# IEC-Breakout.net
KiCad netlist of a schematic drawn in EAGLE
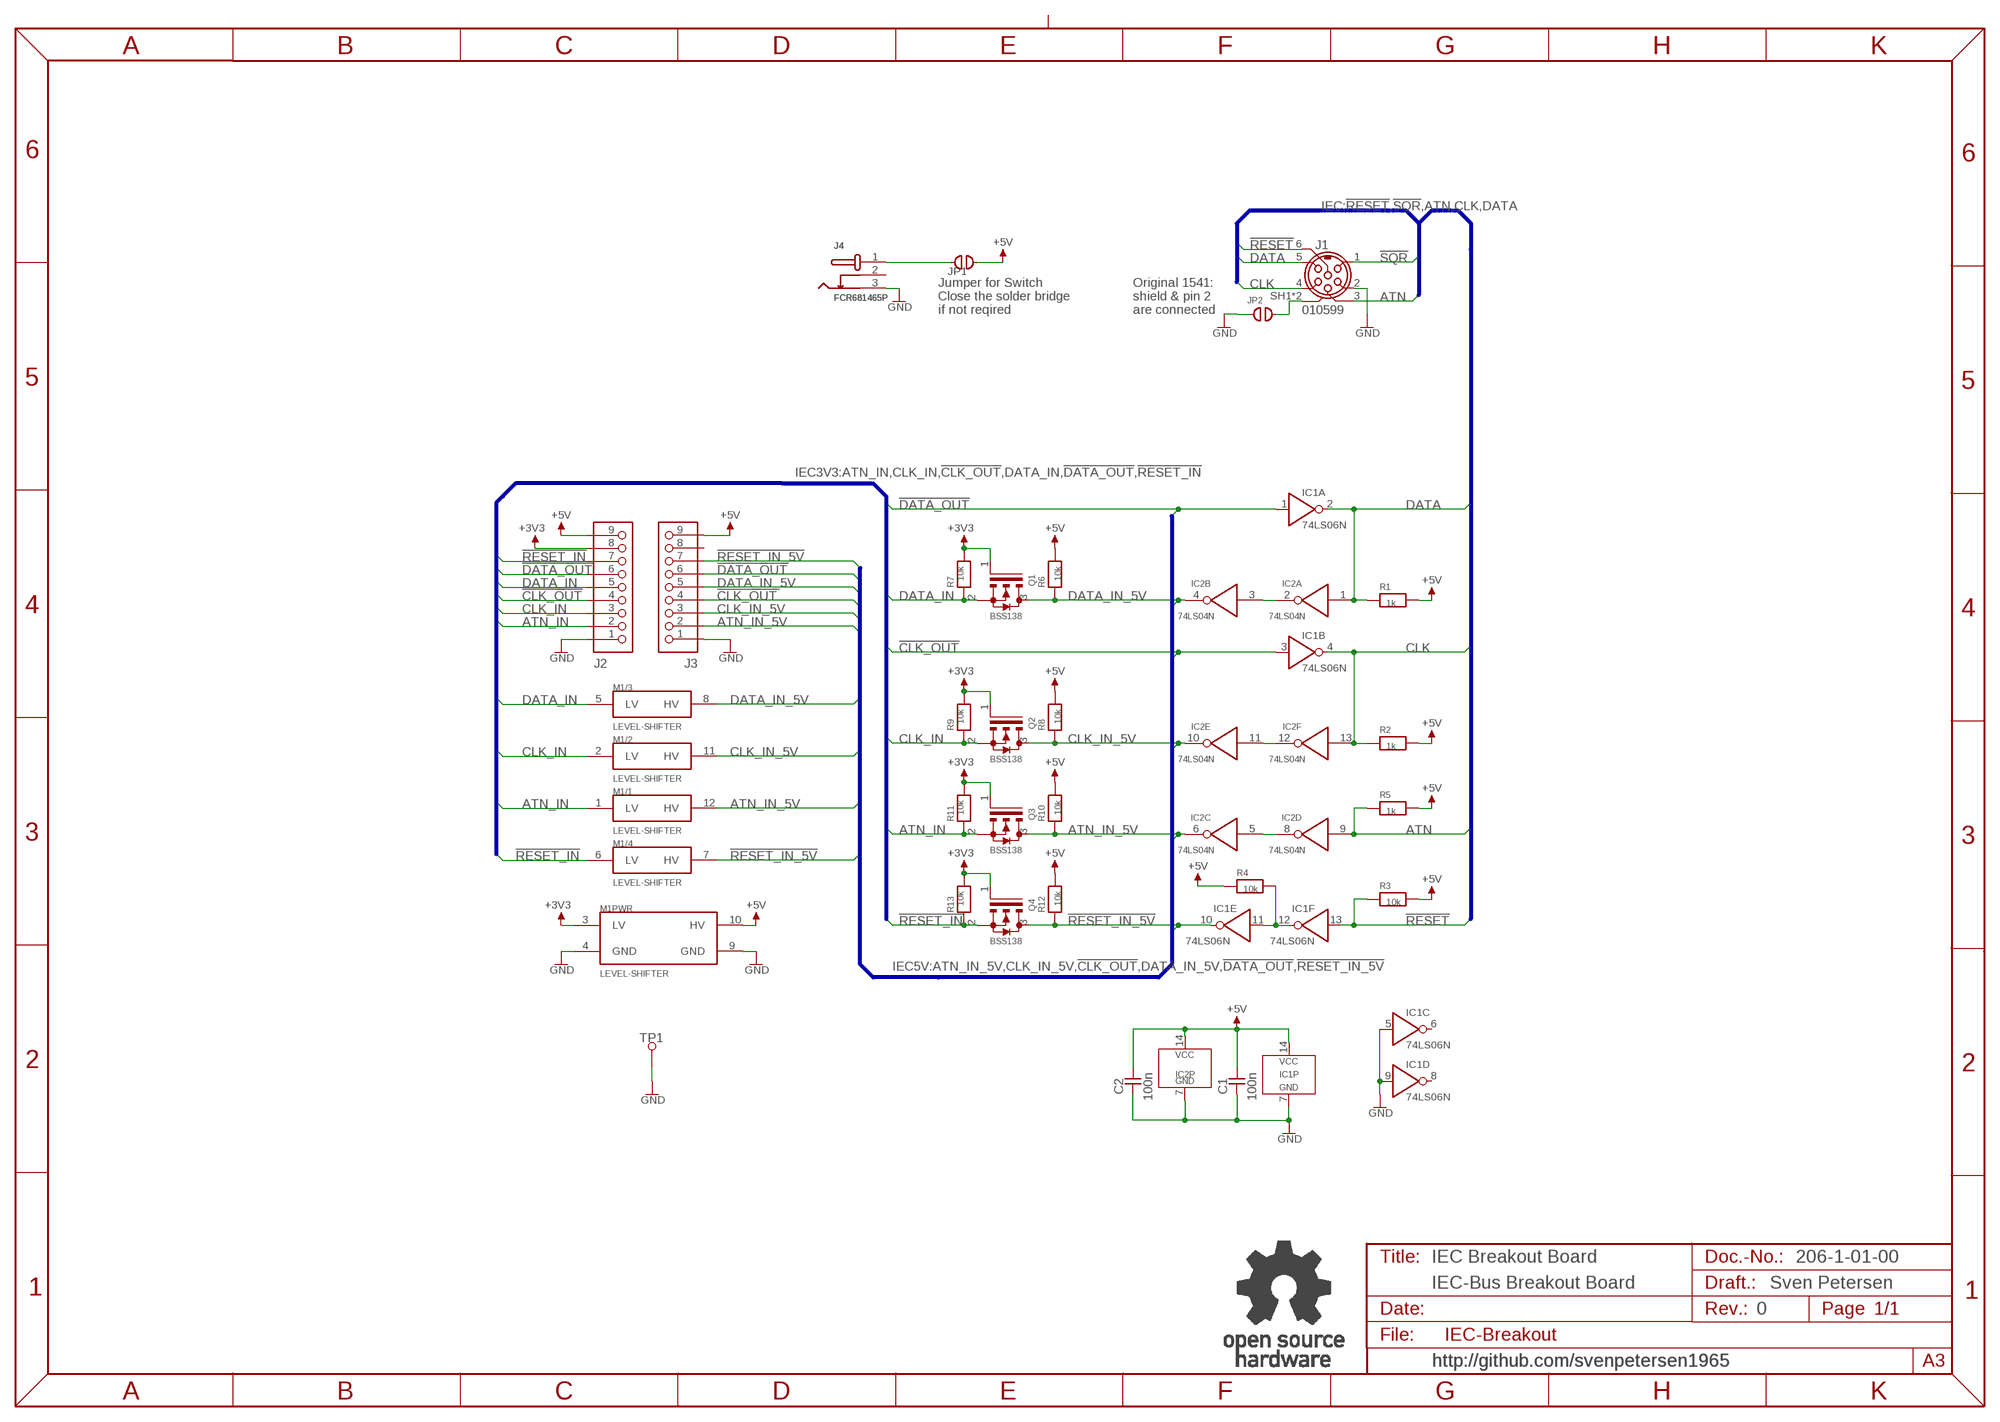
[diagram p0: schematic, sheet 1]

(export (version "E")
  (design (tool "Eeschema 10.0.6"))
  (components
    (comp (ref "C1")
      (value "100n")
      (footprint "eagle-import:C-2,5")
      (libsource (lib "eagle-import") (part "CAP01"))
    )
    (comp (ref "C2")
      (value "100n")
      (footprint "eagle-import:C-2,5")
      (libsource (lib "eagle-import") (part "CAP01"))
    )
    (comp (ref "IC1")
      (value "74LS06N")
      (footprint "eagle-import:DIL-14")
      (libsource (lib "eagle-import") (part "7406N"))
    )
    (comp (ref "IC2")
      (value "74LS04N")
      (footprint "eagle-import:DIL-14")
      (libsource (lib "eagle-import") (part "7404N"))
    )
    (comp (ref "J1")
      (value "010599")
      (footprint "eagle-import:010599")
      (libsource (lib "eagle-import") (part "010599"))
    )
    (comp (ref "J2")
      (value "PINHD-1X9")
      (footprint "eagle-import:1X09")
      (libsource (lib "eagle-import") (part "PINHD-1X9"))
    )
    (comp (ref "J3")
      (value "PINHD-1X9")
      (footprint "eagle-import:1X09")
      (libsource (lib "eagle-import") (part "PINHD-1X9"))
    )
    (comp (ref "J4")
      (value "FCR681465P")
      (footprint "eagle-import:FCR681465P")
      (libsource (lib "eagle-import") (part "FCR681465P"))
    )
    (comp (ref "JP1")
      (value "COMBI_2P")
      (footprint "eagle-import:COMBI-2P")
      (libsource (lib "eagle-import") (part "COMBI_2P"))
    )
    (comp (ref "JP2")
      (value "OPEN")
      (footprint "eagle-import:CP_OP")
      (libsource (lib "eagle-import") (part "OPEN"))
    )
    (comp (ref "M1")
      (value "LEVEL-SHIFTER")
      (footprint "eagle-import:L-SHIFTER")
      (libsource (lib "eagle-import") (part "LEVEL-SHIFTER"))
    )
    (comp (ref "Q1")
      (value "BSS138")
      (footprint "eagle-import:SOT23")
      (libsource (lib "eagle-import") (part "BSS138"))
    )
    (comp (ref "Q2")
      (value "BSS138")
      (footprint "eagle-import:SOT23")
      (libsource (lib "eagle-import") (part "BSS138"))
    )
    (comp (ref "Q3")
      (value "BSS138")
      (footprint "eagle-import:SOT23")
      (libsource (lib "eagle-import") (part "BSS138"))
    )
    (comp (ref "Q4")
      (value "BSS138")
      (footprint "eagle-import:SOT23")
      (libsource (lib "eagle-import") (part "BSS138"))
    )
    (comp (ref "R1")
      (value "1k")
      (footprint "eagle-import:R-10")
      (libsource (lib "eagle-import") (part "RES04"))
    )
    (comp (ref "R2")
      (value "1k")
      (footprint "eagle-import:R-10")
      (libsource (lib "eagle-import") (part "RES04"))
    )
    (comp (ref "R3")
      (value "10k")
      (footprint "eagle-import:R-10")
      (libsource (lib "eagle-import") (part "RES04"))
    )
    (comp (ref "R4")
      (value "10k")
      (footprint "eagle-import:R-10")
      (libsource (lib "eagle-import") (part "RES04"))
    )
    (comp (ref "R5")
      (value "1k")
      (footprint "eagle-import:R-10")
      (libsource (lib "eagle-import") (part "RES04"))
    )
    (comp (ref "R6")
      (value "10k")
      (footprint "eagle-import:0805")
      (libsource (lib "eagle-import") (part "R-0805"))
    )
    (comp (ref "R7")
      (value "10k")
      (footprint "eagle-import:0805")
      (libsource (lib "eagle-import") (part "R-0805"))
    )
    (comp (ref "R8")
      (value "10k")
      (footprint "eagle-import:0805")
      (libsource (lib "eagle-import") (part "R-0805"))
    )
    (comp (ref "R9")
      (value "10k")
      (footprint "eagle-import:0805")
      (libsource (lib "eagle-import") (part "R-0805"))
    )
    (comp (ref "R10")
      (value "10k")
      (footprint "eagle-import:0805")
      (libsource (lib "eagle-import") (part "R-0805"))
    )
    (comp (ref "R11")
      (value "10k")
      (footprint "eagle-import:0805")
      (libsource (lib "eagle-import") (part "R-0805"))
    )
    (comp (ref "R12")
      (value "10k")
      (footprint "eagle-import:0805")
      (libsource (lib "eagle-import") (part "R-0805"))
    )
    (comp (ref "R13")
      (value "10k")
      (footprint "eagle-import:0805")
      (libsource (lib "eagle-import") (part "R-0805"))
    )
    (comp (ref "TP1")
      (value "L1,2_R")
      (footprint "eagle-import:1,2MM_R")
      (libsource (lib "eagle-import") (part "L1,2_R"))
    )
    (comp (ref "U$31")
      (value "OPEN_SOURCE_HW")
      (footprint "eagle-import:OPENHW")
      (libsource (lib "eagle-import") (part "OPEN_SOURCE_HW"))
    )
  )
  (nets
    (net (code "4") (name "+3V3") (class "Default")
      (node (ref "J2") (pin "8") (pinfunction "8_8") (pintype "passive"))
      (node (ref "M1") (pin "3") (pinfunction "LV_3") (pintype "bidirectional"))
      (node (ref "Q1") (pin "1") (pinfunction "G_1") (pintype "bidirectional"))
      (node (ref "Q2") (pin "1") (pinfunction "G_1") (pintype "bidirectional"))
      (node (ref "Q3") (pin "1") (pinfunction "G_1") (pintype "bidirectional"))
      (node (ref "Q4") (pin "1") (pinfunction "G_1") (pintype "bidirectional"))
      (node (ref "R11") (pin "2") (pinfunction "2_2") (pintype "passive"))
      (node (ref "R13") (pin "2") (pinfunction "2_2") (pintype "passive"))
      (node (ref "R7") (pin "2") (pinfunction "2_2") (pintype "passive"))
      (node (ref "R9") (pin "2") (pinfunction "2_2") (pintype "passive"))
    )
    (net (code "5") (name "+5V") (class "Default")
      (node (ref "C1") (pin "2") (pinfunction "2_2") (pintype "passive"))
      (node (ref "C2") (pin "2") (pinfunction "2_2") (pintype "passive"))
      (node (ref "IC1") (pin "14") (pinfunction "VCC_14") (pintype "bidirectional"))
      (node (ref "IC2") (pin "14") (pinfunction "VCC_14") (pintype "bidirectional"))
      (node (ref "J2") (pin "9") (pinfunction "9_9") (pintype "passive"))
      (node (ref "J3") (pin "9") (pinfunction "9_9") (pintype "passive"))
      (node (ref "JP1") (pin "2") (pinfunction "2_2") (pintype "passive"))
      (node (ref "M1") (pin "10") (pinfunction "HV_10") (pintype "bidirectional"))
      (node (ref "R1") (pin "2") (pinfunction "2_2") (pintype "passive"))
      (node (ref "R10") (pin "2") (pinfunction "2_2") (pintype "passive"))
      (node (ref "R12") (pin "2") (pinfunction "2_2") (pintype "passive"))
      (node (ref "R2") (pin "2") (pinfunction "2_2") (pintype "passive"))
      (node (ref "R3") (pin "2") (pinfunction "2_2") (pintype "passive"))
      (node (ref "R4") (pin "1") (pinfunction "1_1") (pintype "passive"))
      (node (ref "R5") (pin "2") (pinfunction "2_2") (pintype "passive"))
      (node (ref "R6") (pin "2") (pinfunction "2_2") (pintype "passive"))
      (node (ref "R8") (pin "2") (pinfunction "2_2") (pintype "passive"))
    )
    (net (code "6") (name "/ATN") (class "Default")
      (node (ref "IC2") (pin "9") (pinfunction "I_9") (pintype "input"))
      (node (ref "J1") (pin "3") (pinfunction "3_3") (pintype "bidirectional"))
      (node (ref "R5") (pin "1") (pinfunction "1_1") (pintype "passive"))
    )
    (net (code "7") (name "/ATN_IN") (class "Default")
      (node (ref "J2") (pin "2") (pinfunction "2_2") (pintype "passive"))
      (node (ref "M1") (pin "1") (pinfunction "LV_1") (pintype "bidirectional"))
      (node (ref "Q3") (pin "2") (pinfunction "S_2") (pintype "bidirectional"))
      (node (ref "R11") (pin "1") (pinfunction "1_1") (pintype "passive"))
    )
    (net (code "8") (name "/ATN_IN_5V") (class "Default")
      (node (ref "IC2") (pin "6") (pinfunction "O_6") (pintype "output"))
      (node (ref "J3") (pin "2") (pinfunction "2_2") (pintype "passive"))
      (node (ref "M1") (pin "12") (pinfunction "HV_12") (pintype "bidirectional"))
      (node (ref "Q3") (pin "3") (pinfunction "D_3") (pintype "bidirectional"))
      (node (ref "R10") (pin "1") (pinfunction "1_1") (pintype "passive"))
    )
    (net (code "9") (name "/CLK") (class "Default")
      (node (ref "IC1") (pin "4") (pinfunction "O_4") (pintype "open_collector"))
      (node (ref "IC2") (pin "13") (pinfunction "I_13") (pintype "input"))
      (node (ref "J1") (pin "4") (pinfunction "4_4") (pintype "bidirectional"))
      (node (ref "R2") (pin "1") (pinfunction "1_1") (pintype "passive"))
    )
    (net (code "10") (name "/CLK_IN") (class "Default")
      (node (ref "J2") (pin "3") (pinfunction "3_3") (pintype "passive"))
      (node (ref "M1") (pin "2") (pinfunction "LV_2") (pintype "bidirectional"))
      (node (ref "Q2") (pin "2") (pinfunction "S_2") (pintype "bidirectional"))
      (node (ref "R9") (pin "1") (pinfunction "1_1") (pintype "passive"))
    )
    (net (code "11") (name "/CLK_IN_5V") (class "Default")
      (node (ref "IC2") (pin "10") (pinfunction "O_10") (pintype "output"))
      (node (ref "J3") (pin "3") (pinfunction "3_3") (pintype "passive"))
      (node (ref "M1") (pin "11") (pinfunction "HV_11") (pintype "bidirectional"))
      (node (ref "Q2") (pin "3") (pinfunction "D_3") (pintype "bidirectional"))
      (node (ref "R8") (pin "1") (pinfunction "1_1") (pintype "passive"))
    )
    (net (code "12") (name "/DATA") (class "Default")
      (node (ref "IC1") (pin "2") (pinfunction "O_2") (pintype "open_collector"))
      (node (ref "IC2") (pin "1") (pinfunction "I_1") (pintype "input"))
      (node (ref "J1") (pin "5") (pinfunction "5_5") (pintype "bidirectional"))
      (node (ref "R1") (pin "1") (pinfunction "1_1") (pintype "passive"))
    )
    (net (code "13") (name "/DATA_IN") (class "Default")
      (node (ref "J2") (pin "5") (pinfunction "5_5") (pintype "passive"))
      (node (ref "M1") (pin "5") (pinfunction "LV_5") (pintype "bidirectional"))
      (node (ref "Q1") (pin "2") (pinfunction "S_2") (pintype "bidirectional"))
      (node (ref "R7") (pin "1") (pinfunction "1_1") (pintype "passive"))
    )
    (net (code "14") (name "/DATA_IN_5V") (class "Default")
      (node (ref "IC2") (pin "4") (pinfunction "O_4") (pintype "output"))
      (node (ref "J3") (pin "5") (pinfunction "5_5") (pintype "passive"))
      (node (ref "M1") (pin "8") (pinfunction "HV_8") (pintype "bidirectional"))
      (node (ref "Q1") (pin "3") (pinfunction "D_3") (pintype "bidirectional"))
      (node (ref "R6") (pin "1") (pinfunction "1_1") (pintype "passive"))
    )
    (net (code "18") (name "/~{CLK_OUT}") (class "Default")
      (node (ref "IC1") (pin "3") (pinfunction "I_3") (pintype "input"))
      (node (ref "J2") (pin "4") (pinfunction "4_4") (pintype "passive"))
      (node (ref "J3") (pin "4") (pinfunction "4_4") (pintype "passive"))
    )
    (net (code "19") (name "/~{DATA_OUT}") (class "Default")
      (node (ref "IC1") (pin "1") (pinfunction "I_1") (pintype "input"))
      (node (ref "J2") (pin "6") (pinfunction "6_6") (pintype "passive"))
      (node (ref "J3") (pin "6") (pinfunction "6_6") (pintype "passive"))
    )
    (net (code "20") (name "/~{RESET_IN_5V}") (class "Default")
      (node (ref "IC1") (pin "10") (pinfunction "O_10") (pintype "open_collector"))
      (node (ref "J3") (pin "7") (pinfunction "7_7") (pintype "passive"))
      (node (ref "M1") (pin "7") (pinfunction "HV_7") (pintype "bidirectional"))
      (node (ref "Q4") (pin "3") (pinfunction "D_3") (pintype "bidirectional"))
      (node (ref "R12") (pin "1") (pinfunction "1_1") (pintype "passive"))
    )
    (net (code "21") (name "/~{RESET_IN}") (class "Default")
      (node (ref "J2") (pin "7") (pinfunction "7_7") (pintype "passive"))
      (node (ref "M1") (pin "6") (pinfunction "LV_6") (pintype "bidirectional"))
      (node (ref "Q4") (pin "2") (pinfunction "S_2") (pintype "bidirectional"))
      (node (ref "R13") (pin "1") (pinfunction "1_1") (pintype "passive"))
    )
    (net (code "22") (name "/~{RESET}") (class "Default")
      (node (ref "IC1") (pin "13") (pinfunction "I_13") (pintype "input"))
      (node (ref "J1") (pin "6") (pinfunction "6_6") (pintype "bidirectional"))
      (node (ref "R3") (pin "1") (pinfunction "1_1") (pintype "passive"))
    )
    (net (code "23") (name "/~{SQR}") (class "Default")
      (node (ref "J1") (pin "1") (pinfunction "1_1") (pintype "bidirectional"))
    )
    (net (code "24") (name "GND") (class "Default")
      (node (ref "C1") (pin "1") (pinfunction "1_1") (pintype "passive"))
      (node (ref "C2") (pin "1") (pinfunction "1_1") (pintype "passive"))
      (node (ref "IC1") (pin "5") (pinfunction "I_5") (pintype "input"))
      (node (ref "IC1") (pin "7") (pinfunction "GND_7") (pintype "bidirectional"))
      (node (ref "IC1") (pin "9") (pinfunction "I_9") (pintype "input"))
      (node (ref "IC2") (pin "7") (pinfunction "GND_7") (pintype "bidirectional"))
      (node (ref "J1") (pin "2") (pinfunction "2_2") (pintype "bidirectional"))
      (node (ref "J2") (pin "1") (pinfunction "1_1") (pintype "passive"))
      (node (ref "J3") (pin "1") (pinfunction "1_1") (pintype "passive"))
      (node (ref "J4") (pin "3") (pinfunction "3_3") (pintype "bidirectional"))
      (node (ref "JP2") (pin "1") (pinfunction "1_1") (pintype "passive"))
      (node (ref "M1") (pin "4") (pinfunction "GND_4") (pintype "bidirectional"))
      (node (ref "M1") (pin "9") (pinfunction "GND_9") (pintype "bidirectional"))
      (node (ref "TP1") (pin "1") (pinfunction "1_1") (pintype "passive"))
    )
    (net (code "25") (name "Net-(IC1E-I)") (class "Default")
      (node (ref "IC1") (pin "11") (pinfunction "I_11") (pintype "input"))
      (node (ref "IC1") (pin "12") (pinfunction "O_12") (pintype "open_collector"))
      (node (ref "R4") (pin "2") (pinfunction "2_2") (pintype "passive"))
    )
    (net (code "26") (name "Net-(IC2A-O)") (class "Default")
      (node (ref "IC2") (pin "2") (pinfunction "O_2") (pintype "output"))
      (node (ref "IC2") (pin "3") (pinfunction "I_3") (pintype "input"))
    )
    (net (code "27") (name "Net-(IC2C-I)") (class "Default")
      (node (ref "IC2") (pin "5") (pinfunction "I_5") (pintype "input"))
      (node (ref "IC2") (pin "8") (pinfunction "O_8") (pintype "output"))
    )
    (net (code "28") (name "Net-(IC2E-I)") (class "Default")
      (node (ref "IC2") (pin "11") (pinfunction "I_11") (pintype "input"))
      (node (ref "IC2") (pin "12") (pinfunction "O_12") (pintype "output"))
    )
    (net (code "29") (name "Net-(J1-SH-PadSH1)") (class "Default")
      (node (ref "J1") (pin "SH1") (pinfunction "SH_SH1") (pintype "bidirectional"))
      (node (ref "J1") (pin "SH2") (pinfunction "SH_SH2") (pintype "bidirectional"))
      (node (ref "JP2") (pin "2") (pinfunction "2_2") (pintype "passive"))
    )
    (net (code "30") (name "Net-(J4-Pad1)") (class "Default")
      (node (ref "J4") (pin "1") (pinfunction "1_1") (pintype "bidirectional"))
      (node (ref "JP1") (pin "1") (pinfunction "1_1") (pintype "passive"))
    )
    (net (code "31") (name "unconnected-(IC1C-O-Pad6)") (class "Default")
      (node (ref "IC1") (pin "6") (pinfunction "O_6") (pintype "open_collector"))
    )
    (net (code "32") (name "unconnected-(IC1D-O-Pad8)") (class "Default")
      (node (ref "IC1") (pin "8") (pinfunction "O_8") (pintype "open_collector"))
    )
    (net (code "33") (name "unconnected-(J3-Pad8)") (class "Default")
      (node (ref "J3") (pin "8") (pinfunction "8_8") (pintype "passive"))
    )
    (net (code "34") (name "unconnected-(J4-Pad2)") (class "Default")
      (node (ref "J4") (pin "2") (pinfunction "2_2") (pintype "bidirectional"))
    )
  )
)
